# light_45.net
KiCad netlist of a schematic drawn in EAGLE
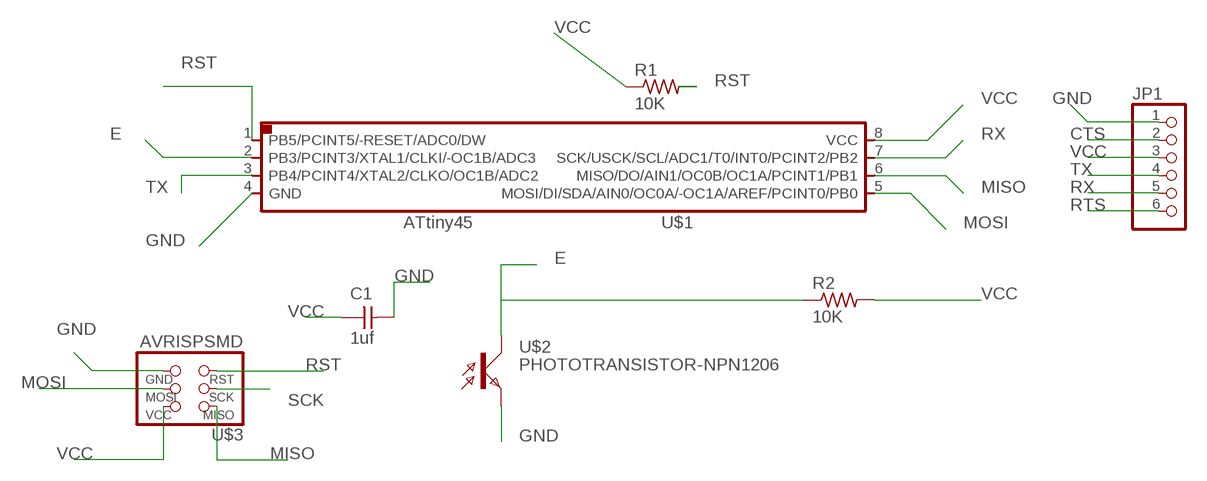
[diagram p0: schematic, sheet 1]

(export (version "E")
  (design (tool "Eeschema 10.0.6"))
  (components
    (comp (ref "C1")
      (value "1uf")
      (footprint "eagle-import:1206")
      (libsource (lib "eagle-import") (part "UNPOLARIZED_CAPACITOR1206"))
    )
    (comp (ref "JP1")
      (value "PINHD-1X6B")
      (footprint "eagle-import:1X06-BIG")
      (libsource (lib "eagle-import") (part "PINHD-1X6B"))
    )
    (comp (ref "R1")
      (value "10K")
      (footprint "eagle-import:R1206FAB")
      (libsource (lib "eagle-import") (part "RES-US1206FAB"))
    )
    (comp (ref "R2")
      (value "10K")
      (footprint "eagle-import:R1206FAB")
      (libsource (lib "eagle-import") (part "RES-US1206FAB"))
    )
    (comp (ref "U$1")
      (value "ATTINY45SI")
      (footprint "eagle-import:SOIC8")
      (libsource (lib "eagle-import") (part "ATTINY45SI"))
    )
    (comp (ref "U$2")
      (value "PHOTOTRANSISTOR-NPN1206")
      (footprint "eagle-import:OP1206")
      (libsource (lib "eagle-import") (part "PHOTOTRANSISTOR-NPN1206"))
    )
    (comp (ref "U$3")
      (value "AVRISPSMD")
      (footprint "eagle-import:2X03SMD")
      (libsource (lib "eagle-import") (part "AVRISPSMD"))
    )
  )
  (nets
    (net (code "1") (name "/CTS") (class "Default")
      (node (ref "JP1") (pin "2") (pinfunction "2_2") (pintype "passive"))
    )
    (net (code "2") (name "/E") (class "Default")
      (node (ref "R2") (pin "1") (pinfunction "1_1") (pintype "passive"))
      (node (ref "U$1") (pin "2") (pinfunction "PB3/PCINT3/XTAL1/CLKI/-OC1B/ADC3_2") (pintype "bidirectional"))
      (node (ref "U$2") (pin "COLLECTOR") (pinfunction "C_COLLECTOR") (pintype "passive"))
    )
    (net (code "3") (name "/GND") (class "Default")
      (node (ref "C1") (pin "2") (pinfunction "2_2") (pintype "passive"))
      (node (ref "JP1") (pin "1") (pinfunction "1_1") (pintype "passive"))
      (node (ref "U$1") (pin "4") (pinfunction "GND_4") (pintype "bidirectional"))
      (node (ref "U$2") (pin "EMITTER") (pinfunction "E_EMITTER") (pintype "passive"))
      (node (ref "U$3") (pin "6") (pinfunction "GND_6") (pintype "passive"))
    )
    (net (code "4") (name "/MISO") (class "Default")
      (node (ref "U$1") (pin "6") (pinfunction "MISO/DO/AIN1/OC0B/OC1A/PCINT1/PB1_6") (pintype "bidirectional"))
      (node (ref "U$3") (pin "1") (pinfunction "MISO_1") (pintype "passive"))
    )
    (net (code "5") (name "/MOSI") (class "Default")
      (node (ref "U$1") (pin "5") (pinfunction "MOSI/DI/SDA/AIN0/OC0A/-OC1A/AREF/PCINT0/PB0_5") (pintype "bidirectional"))
      (node (ref "U$3") (pin "4") (pinfunction "MOSI_4") (pintype "passive"))
    )
    (net (code "6") (name "/RST") (class "Default")
      (node (ref "R1") (pin "2") (pinfunction "2_2") (pintype "passive"))
      (node (ref "U$1") (pin "1") (pinfunction "PB5/PCINT5/-RESET/ADC0/DW_1") (pintype "bidirectional"))
      (node (ref "U$3") (pin "5") (pinfunction "RST_5") (pintype "passive"))
    )
    (net (code "7") (name "/RTS") (class "Default")
      (node (ref "JP1") (pin "6") (pinfunction "6_6") (pintype "passive"))
    )
    (net (code "8") (name "/RX") (class "Default")
      (node (ref "JP1") (pin "5") (pinfunction "5_5") (pintype "passive"))
      (node (ref "U$1") (pin "7") (pinfunction "SCK/USCK/SCL/ADC1/T0/INT0/PCINT2/PB2_7") (pintype "bidirectional"))
    )
    (net (code "9") (name "/SCK") (class "Default")
      (node (ref "U$3") (pin "3") (pinfunction "SCK_3") (pintype "passive"))
    )
    (net (code "10") (name "/TX") (class "Default")
      (node (ref "JP1") (pin "4") (pinfunction "4_4") (pintype "passive"))
      (node (ref "U$1") (pin "3") (pinfunction "PB4/PCINT4/XTAL2/CLKO/OC1B/ADC2_3") (pintype "bidirectional"))
    )
    (net (code "11") (name "/VCC") (class "Default")
      (node (ref "C1") (pin "1") (pinfunction "1_1") (pintype "passive"))
      (node (ref "JP1") (pin "3") (pinfunction "3_3") (pintype "passive"))
      (node (ref "R1") (pin "1") (pinfunction "1_1") (pintype "passive"))
      (node (ref "R2") (pin "2") (pinfunction "2_2") (pintype "passive"))
      (node (ref "U$1") (pin "8") (pinfunction "VCC_8") (pintype "bidirectional"))
      (node (ref "U$3") (pin "2") (pinfunction "VCC_2") (pintype "passive"))
    )
  )
)
